# eduBoard.net
KiCad netlist of a schematic drawn in EAGLE
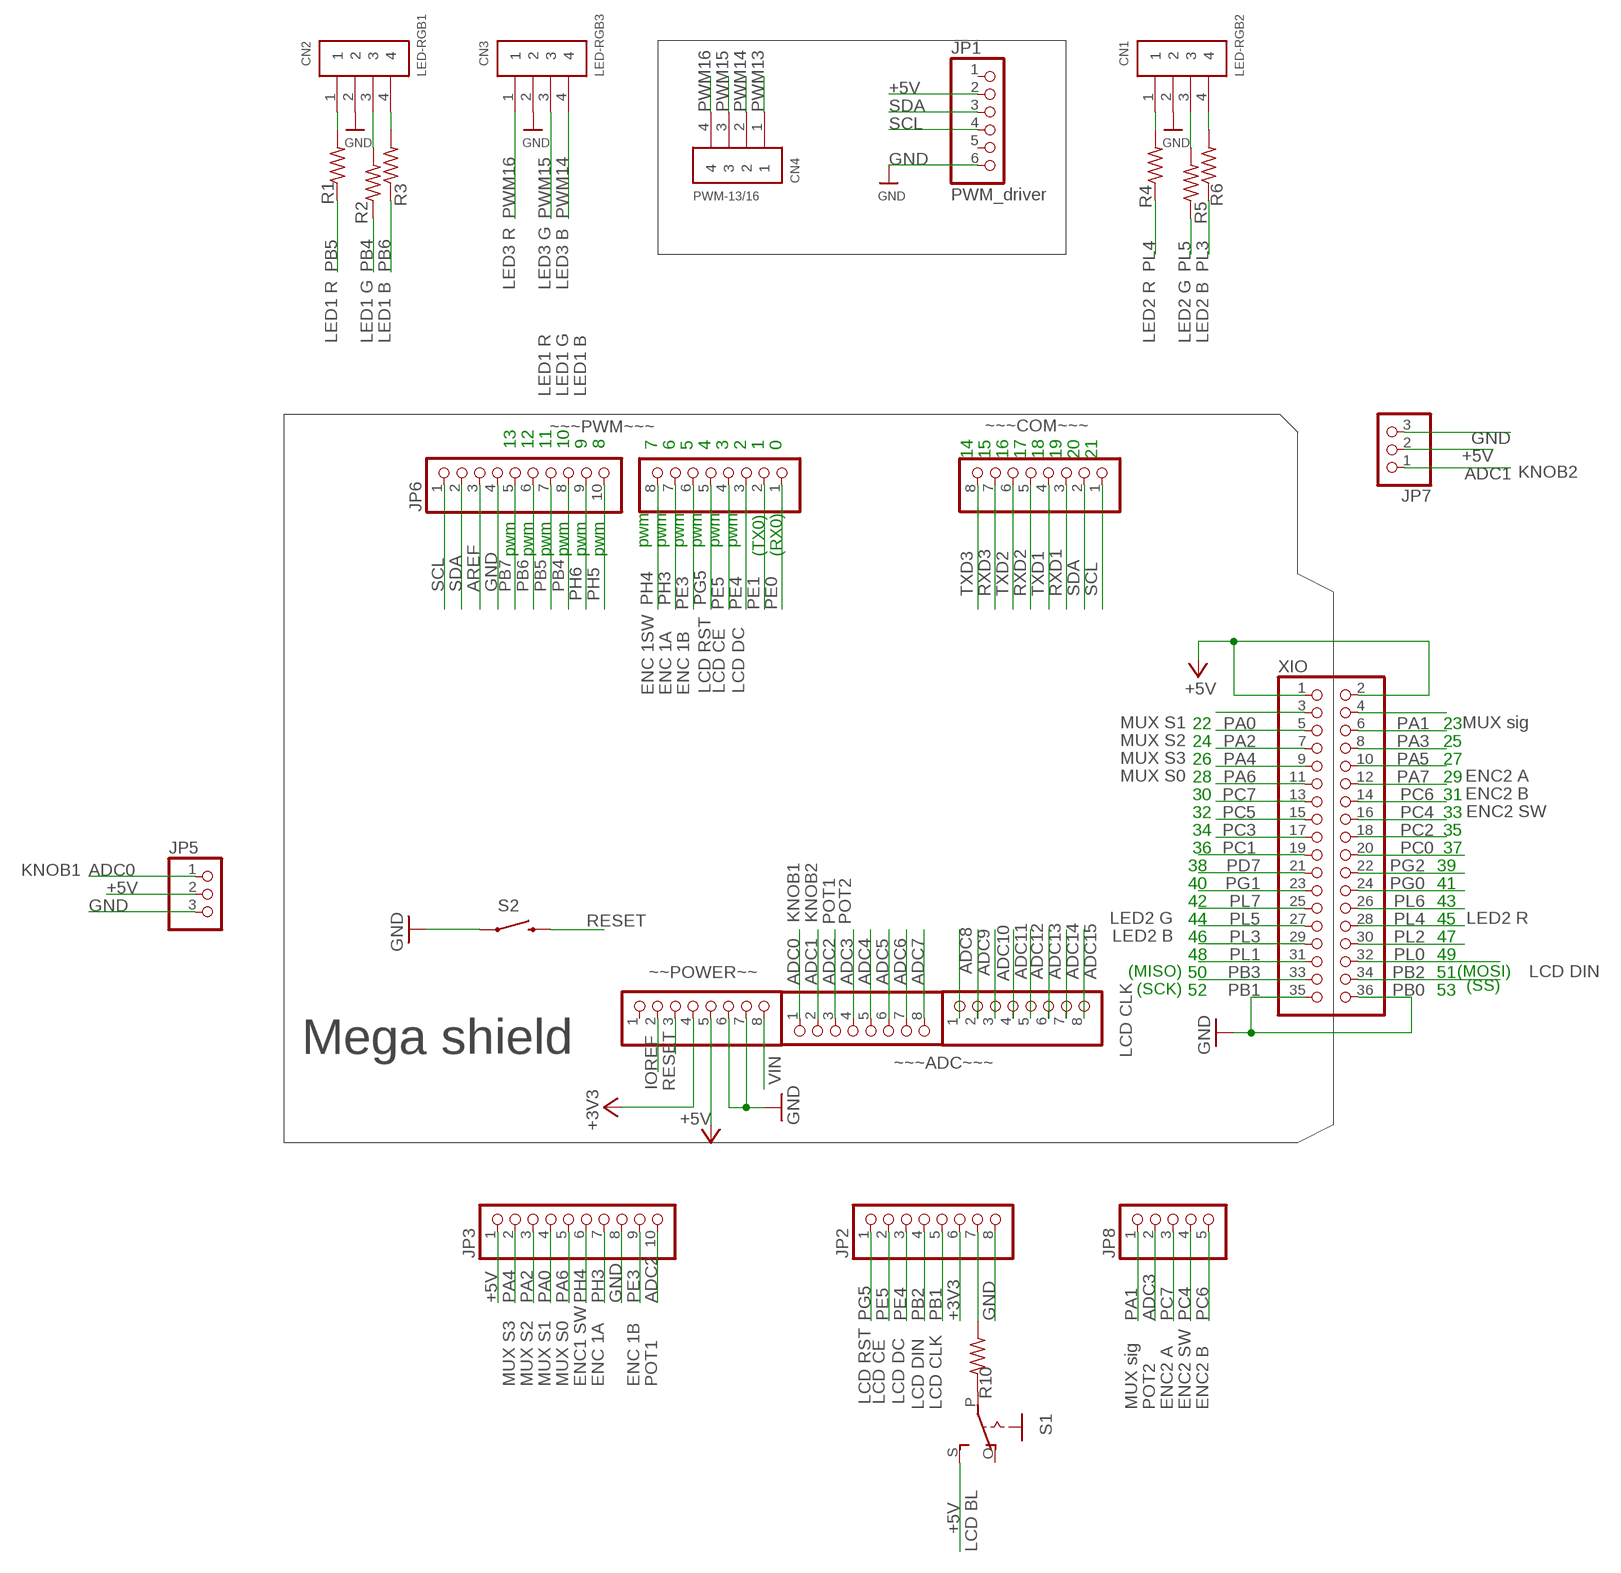
[diagram p0: schematic, sheet 1]

(export (version "E")
  (design (tool "Eeschema 10.0.6"))
  (components
    (comp (ref "ADCL")
      (value "8x1F-H8.5")
      (footprint "eagle-import:1X08")
      (libsource (lib "eagle-import") (part "PINHD-1X8"))
    )
    (comp (ref "CN1")
      (value "LED-RGB2")
      (footprint "eagle-import:1X04-BIG")
      (libsource (lib "eagle-import") (part "1X4-BIG"))
    )
    (comp (ref "CN2")
      (value "LED-RGB1")
      (footprint "eagle-import:1X04-BIG")
      (libsource (lib "eagle-import") (part "1X4-BIG"))
    )
    (comp (ref "CN3")
      (value "LED-RGB3")
      (footprint "eagle-import:1X04-BIG")
      (libsource (lib "eagle-import") (part "1X4-BIG"))
    )
    (comp (ref "CN4")
      (value "PWM-13/16")
      (footprint "eagle-import:1X04-BIG")
      (libsource (lib "eagle-import") (part "1X4-BIG"))
    )
    (comp (ref "JP1")
      (value "PWM_driver")
      (footprint "eagle-import:1X06")
      (libsource (lib "eagle-import") (part "PINHD-1X6"))
    )
    (comp (ref "JP2")
      (value "PINHD-1X8OVAL")
      (footprint "eagle-import:1X08-OVAL")
      (libsource (lib "eagle-import") (part "PINHD-1X8OVAL"))
    )
    (comp (ref "JP3")
      (value "PINHD-1X10_ARD")
      (footprint "eagle-import:1X10")
      (libsource (lib "eagle-import") (part "eduBoard_PINHD-1X10_ARD"))
    )
    (comp (ref "JP5")
      (value "PINHD-1X3")
      (footprint "eagle-import:1X03")
      (libsource (lib "eagle-import") (part "PINHD-1X3"))
    )
    (comp (ref "JP6")
      (value "10x1F-H8.5")
      (footprint "eagle-import:1X10")
      (libsource (lib "eagle-import") (part "PINHD-1X10_ARD"))
    )
    (comp (ref "JP7")
      (value "PINHD-1X3")
      (footprint "eagle-import:1X03")
      (libsource (lib "eagle-import") (part "PINHD-1X3"))
    )
    (comp (ref "JP8")
      (value "HEADER-1X5")
      (footprint "eagle-import:1X05_OVAL")
      (libsource (lib "eagle-import") (part "HEADER-1X5"))
    )
    (comp (ref "R1")
      (value "R-US_0207/10")
      (footprint "eagle-import:0207_10")
      (libsource (lib "eagle-import") (part "R-US_0207/10"))
    )
    (comp (ref "R2")
      (value "R-US_0207/10")
      (footprint "eagle-import:0207_10")
      (libsource (lib "eagle-import") (part "R-US_0207/10"))
    )
    (comp (ref "R3")
      (value "R-US_0207/10")
      (footprint "eagle-import:0207_10")
      (libsource (lib "eagle-import") (part "R-US_0207/10"))
    )
    (comp (ref "R4")
      (value "R-US_0207/10")
      (footprint "eagle-import:0207_10")
      (libsource (lib "eagle-import") (part "R-US_0207/10"))
    )
    (comp (ref "R5")
      (value "R-US_0207/10")
      (footprint "eagle-import:0207_10")
      (libsource (lib "eagle-import") (part "R-US_0207/10"))
    )
    (comp (ref "R6")
      (value "R-US_0207/10")
      (footprint "eagle-import:0207_10")
      (libsource (lib "eagle-import") (part "R-US_0207/10"))
    )
    (comp (ref "R10")
      (value "R-US_0207/10")
      (footprint "eagle-import:0207_10")
      (libsource (lib "eagle-import") (part "R-US_0207/10"))
    )
    (comp (ref "S1")
      (value "EG1218S")
      (footprint "eagle-import:EG1218")
      (libsource (lib "eagle-import") (part "EG1218S"))
    )
    (comp (ref "S2")
      (value "SWITCH-MOMENTARY-2PTH")
      (footprint "eagle-import:TACTILE-PTH")
      (libsource (lib "eagle-import") (part "SWITCH-MOMENTARY-2PTH"))
    )
    (comp (ref "XIO")
      (value "18x2F-H8.5")
      (footprint "eagle-import:2X18")
      (libsource (lib "eagle-import") (part "PINHD-2X18"))
    )
    (comp (ref "~~POWER~~")
      (value "8x1F-H8.5")
      (footprint "eagle-import:1X08")
      (libsource (lib "eagle-import") (part "PINHD-1X8"))
    )
    (comp (ref "~~~ADC~~~")
      (value "8x1F-H8.5")
      (footprint "eagle-import:1X08")
      (libsource (lib "eagle-import") (part "PINHD-1X8"))
    )
    (comp (ref "~~~COM~~~")
      (value "8x1F-H8.5")
      (footprint "eagle-import:1X08")
      (libsource (lib "eagle-import") (part "PINHD-1X8"))
    )
    (comp (ref "~~~PWM~~~")
      (value "8x1F-H8.5")
      (footprint "eagle-import:1X08")
      (libsource (lib "eagle-import") (part "PINHD-1X8"))
    )
  )
  (nets
    (net (code "1") (name "+3V3") (class "Default")
      (node (ref "JP2") (pin "6") (pinfunction "6_6") (pintype "passive"))
      (node (ref "~~POWER~~") (pin "4") (pinfunction "4_4") (pintype "passive"))
    )
    (net (code "2") (name "+5V") (class "Default")
      (node (ref "JP1") (pin "2") (pinfunction "2_2") (pintype "passive"))
      (node (ref "JP3") (pin "1") (pinfunction "1_1") (pintype "passive"))
      (node (ref "JP5") (pin "2") (pinfunction "2_2") (pintype "passive"))
      (node (ref "JP7") (pin "2") (pinfunction "2_2") (pintype "passive"))
      (node (ref "S1") (pin "S") (pinfunction "S_S") (pintype "passive"))
      (node (ref "XIO") (pin "1") (pinfunction "1_1") (pintype "passive"))
      (node (ref "XIO") (pin "2") (pinfunction "2_2") (pintype "passive"))
      (node (ref "~~POWER~~") (pin "5") (pinfunction "5_5") (pintype "passive"))
    )
    (net (code "3") (name "/ADC0") (class "Default")
      (node (ref "ADCL") (pin "1") (pinfunction "1_1") (pintype "passive"))
      (node (ref "JP5") (pin "1") (pinfunction "1_1") (pintype "passive"))
    )
    (net (code "4") (name "/ADC1") (class "Default")
      (node (ref "ADCL") (pin "2") (pinfunction "2_2") (pintype "passive"))
      (node (ref "JP7") (pin "1") (pinfunction "1_1") (pintype "passive"))
    )
    (net (code "5") (name "/ADC2") (class "Default")
      (node (ref "ADCL") (pin "3") (pinfunction "3_3") (pintype "passive"))
      (node (ref "JP3") (pin "10") (pinfunction "10_10") (pintype "passive"))
    )
    (net (code "6") (name "/ADC3") (class "Default")
      (node (ref "ADCL") (pin "4") (pinfunction "4_4") (pintype "passive"))
      (node (ref "JP8") (pin "2") (pinfunction "2_2") (pintype "passive"))
    )
    (net (code "7") (name "/ADC4") (class "Default")
      (node (ref "ADCL") (pin "5") (pinfunction "5_5") (pintype "passive"))
    )
    (net (code "8") (name "/ADC5") (class "Default")
      (node (ref "ADCL") (pin "6") (pinfunction "6_6") (pintype "passive"))
    )
    (net (code "9") (name "/ADC6") (class "Default")
      (node (ref "ADCL") (pin "7") (pinfunction "7_7") (pintype "passive"))
    )
    (net (code "10") (name "/ADC7") (class "Default")
      (node (ref "ADCL") (pin "8") (pinfunction "8_8") (pintype "passive"))
    )
    (net (code "11") (name "/ADC8") (class "Default")
      (node (ref "~~~ADC~~~") (pin "1") (pinfunction "1_1") (pintype "passive"))
    )
    (net (code "12") (name "/ADC9") (class "Default")
      (node (ref "~~~ADC~~~") (pin "2") (pinfunction "2_2") (pintype "passive"))
    )
    (net (code "13") (name "/ADC10") (class "Default")
      (node (ref "~~~ADC~~~") (pin "3") (pinfunction "3_3") (pintype "passive"))
    )
    (net (code "14") (name "/ADC11") (class "Default")
      (node (ref "~~~ADC~~~") (pin "4") (pinfunction "4_4") (pintype "passive"))
    )
    (net (code "15") (name "/ADC12") (class "Default")
      (node (ref "~~~ADC~~~") (pin "5") (pinfunction "5_5") (pintype "passive"))
    )
    (net (code "16") (name "/ADC13") (class "Default")
      (node (ref "~~~ADC~~~") (pin "6") (pinfunction "6_6") (pintype "passive"))
    )
    (net (code "17") (name "/ADC14") (class "Default")
      (node (ref "~~~ADC~~~") (pin "7") (pinfunction "7_7") (pintype "passive"))
    )
    (net (code "18") (name "/ADC15") (class "Default")
      (node (ref "~~~ADC~~~") (pin "8") (pinfunction "8_8") (pintype "passive"))
    )
    (net (code "19") (name "/AREF") (class "Default")
      (node (ref "JP6") (pin "3") (pinfunction "3_3") (pintype "passive"))
    )
    (net (code "20") (name "/IOREF") (class "Default")
      (node (ref "~~POWER~~") (pin "2") (pinfunction "2_2") (pintype "passive"))
    )
    (net (code "21") (name "/PA0") (class "Default")
      (node (ref "JP3") (pin "4") (pinfunction "4_4") (pintype "passive"))
      (node (ref "XIO") (pin "3") (pinfunction "3_3") (pintype "passive"))
    )
    (net (code "22") (name "/PA1") (class "Default")
      (node (ref "JP8") (pin "1") (pinfunction "1_1") (pintype "passive"))
      (node (ref "XIO") (pin "4") (pinfunction "4_4") (pintype "passive"))
    )
    (net (code "23") (name "/PA2") (class "Default")
      (node (ref "JP3") (pin "3") (pinfunction "3_3") (pintype "passive"))
      (node (ref "XIO") (pin "5") (pinfunction "5_5") (pintype "passive"))
    )
    (net (code "24") (name "/PA3") (class "Default")
      (node (ref "XIO") (pin "6") (pinfunction "6_6") (pintype "passive"))
    )
    (net (code "25") (name "/PA4") (class "Default")
      (node (ref "JP3") (pin "2") (pinfunction "2_2") (pintype "passive"))
      (node (ref "XIO") (pin "7") (pinfunction "7_7") (pintype "passive"))
    )
    (net (code "26") (name "/PA5") (class "Default")
      (node (ref "XIO") (pin "8") (pinfunction "8_8") (pintype "passive"))
    )
    (net (code "27") (name "/PA6") (class "Default")
      (node (ref "JP3") (pin "5") (pinfunction "5_5") (pintype "passive"))
      (node (ref "XIO") (pin "9") (pinfunction "9_9") (pintype "passive"))
    )
    (net (code "28") (name "/PA7") (class "Default")
      (node (ref "XIO") (pin "10") (pinfunction "10_10") (pintype "passive"))
    )
    (net (code "29") (name "/PB0") (class "Default")
      (node (ref "XIO") (pin "34") (pinfunction "34_34") (pintype "passive"))
    )
    (net (code "30") (name "/PB1") (class "Default")
      (node (ref "JP2") (pin "5") (pinfunction "5_5") (pintype "passive"))
      (node (ref "XIO") (pin "33") (pinfunction "33_33") (pintype "passive"))
    )
    (net (code "31") (name "/PB2") (class "Default")
      (node (ref "JP2") (pin "4") (pinfunction "4_4") (pintype "passive"))
      (node (ref "XIO") (pin "32") (pinfunction "32_32") (pintype "passive"))
    )
    (net (code "32") (name "/PB3") (class "Default")
      (node (ref "XIO") (pin "31") (pinfunction "31_31") (pintype "passive"))
    )
    (net (code "33") (name "/PB4") (class "Default")
      (node (ref "JP6") (pin "8") (pinfunction "8_8") (pintype "passive"))
      (node (ref "R2") (pin "1") (pinfunction "1_1") (pintype "passive"))
    )
    (net (code "34") (name "/PB5") (class "Default")
      (node (ref "JP6") (pin "7") (pinfunction "7_7") (pintype "passive"))
      (node (ref "R1") (pin "1") (pinfunction "1_1") (pintype "passive"))
    )
    (net (code "35") (name "/PB6") (class "Default")
      (node (ref "JP6") (pin "6") (pinfunction "6_6") (pintype "passive"))
      (node (ref "R3") (pin "1") (pinfunction "1_1") (pintype "passive"))
    )
    (net (code "36") (name "/PB7") (class "Default")
      (node (ref "JP6") (pin "5") (pinfunction "5_5") (pintype "passive"))
    )
    (net (code "37") (name "/PC0") (class "Default")
      (node (ref "XIO") (pin "18") (pinfunction "18_18") (pintype "passive"))
    )
    (net (code "38") (name "/PC1") (class "Default")
      (node (ref "XIO") (pin "17") (pinfunction "17_17") (pintype "passive"))
    )
    (net (code "39") (name "/PC2") (class "Default")
      (node (ref "XIO") (pin "16") (pinfunction "16_16") (pintype "passive"))
    )
    (net (code "40") (name "/PC3") (class "Default")
      (node (ref "XIO") (pin "15") (pinfunction "15_15") (pintype "passive"))
    )
    (net (code "41") (name "/PC4") (class "Default")
      (node (ref "JP8") (pin "4") (pinfunction "4_4") (pintype "passive"))
      (node (ref "XIO") (pin "14") (pinfunction "14_14") (pintype "passive"))
    )
    (net (code "42") (name "/PC5") (class "Default")
      (node (ref "XIO") (pin "13") (pinfunction "13_13") (pintype "passive"))
    )
    (net (code "43") (name "/PC6") (class "Default")
      (node (ref "JP8") (pin "5") (pinfunction "5_5") (pintype "passive"))
      (node (ref "XIO") (pin "12") (pinfunction "12_12") (pintype "passive"))
    )
    (net (code "44") (name "/PC7") (class "Default")
      (node (ref "JP8") (pin "3") (pinfunction "3_3") (pintype "passive"))
      (node (ref "XIO") (pin "11") (pinfunction "11_11") (pintype "passive"))
    )
    (net (code "45") (name "/PD7") (class "Default")
      (node (ref "XIO") (pin "19") (pinfunction "19_19") (pintype "passive"))
    )
    (net (code "46") (name "/PE0") (class "Default")
      (node (ref "~~~PWM~~~") (pin "1") (pinfunction "1_1") (pintype "passive"))
    )
    (net (code "47") (name "/PE1") (class "Default")
      (node (ref "~~~PWM~~~") (pin "2") (pinfunction "2_2") (pintype "passive"))
    )
    (net (code "48") (name "/PE3") (class "Default")
      (node (ref "JP3") (pin "9") (pinfunction "9_9") (pintype "passive"))
      (node (ref "~~~PWM~~~") (pin "6") (pinfunction "6_6") (pintype "passive"))
    )
    (net (code "49") (name "/PE4") (class "Default")
      (node (ref "JP2") (pin "3") (pinfunction "3_3") (pintype "passive"))
      (node (ref "~~~PWM~~~") (pin "3") (pinfunction "3_3") (pintype "passive"))
    )
    (net (code "50") (name "/PE5") (class "Default")
      (node (ref "JP2") (pin "2") (pinfunction "2_2") (pintype "passive"))
      (node (ref "~~~PWM~~~") (pin "4") (pinfunction "4_4") (pintype "passive"))
    )
    (net (code "51") (name "/PG0") (class "Default")
      (node (ref "XIO") (pin "22") (pinfunction "22_22") (pintype "passive"))
    )
    (net (code "52") (name "/PG1") (class "Default")
      (node (ref "XIO") (pin "21") (pinfunction "21_21") (pintype "passive"))
    )
    (net (code "53") (name "/PG2") (class "Default")
      (node (ref "XIO") (pin "20") (pinfunction "20_20") (pintype "passive"))
    )
    (net (code "54") (name "/PG5") (class "Default")
      (node (ref "JP2") (pin "1") (pinfunction "1_1") (pintype "passive"))
      (node (ref "~~~PWM~~~") (pin "5") (pinfunction "5_5") (pintype "passive"))
    )
    (net (code "55") (name "/PH3") (class "Default")
      (node (ref "JP3") (pin "7") (pinfunction "7_7") (pintype "passive"))
      (node (ref "~~~PWM~~~") (pin "7") (pinfunction "7_7") (pintype "passive"))
    )
    (net (code "56") (name "/PH4") (class "Default")
      (node (ref "JP3") (pin "6") (pinfunction "6_6") (pintype "passive"))
      (node (ref "~~~PWM~~~") (pin "8") (pinfunction "8_8") (pintype "passive"))
    )
    (net (code "57") (name "/PH5") (class "Default")
      (node (ref "JP6") (pin "10") (pinfunction "10_10") (pintype "passive"))
    )
    (net (code "58") (name "/PH6") (class "Default")
      (node (ref "JP6") (pin "9") (pinfunction "9_9") (pintype "passive"))
    )
    (net (code "59") (name "/PL0") (class "Default")
      (node (ref "XIO") (pin "30") (pinfunction "30_30") (pintype "passive"))
    )
    (net (code "60") (name "/PL1") (class "Default")
      (node (ref "XIO") (pin "29") (pinfunction "29_29") (pintype "passive"))
    )
    (net (code "61") (name "/PL2") (class "Default")
      (node (ref "XIO") (pin "28") (pinfunction "28_28") (pintype "passive"))
    )
    (net (code "62") (name "/PL3") (class "Default")
      (node (ref "R6") (pin "1") (pinfunction "1_1") (pintype "passive"))
      (node (ref "XIO") (pin "27") (pinfunction "27_27") (pintype "passive"))
    )
    (net (code "63") (name "/PL4") (class "Default")
      (node (ref "R4") (pin "1") (pinfunction "1_1") (pintype "passive"))
      (node (ref "XIO") (pin "26") (pinfunction "26_26") (pintype "passive"))
    )
    (net (code "64") (name "/PL5") (class "Default")
      (node (ref "R5") (pin "1") (pinfunction "1_1") (pintype "passive"))
      (node (ref "XIO") (pin "25") (pinfunction "25_25") (pintype "passive"))
    )
    (net (code "65") (name "/PL6") (class "Default")
      (node (ref "XIO") (pin "24") (pinfunction "24_24") (pintype "passive"))
    )
    (net (code "66") (name "/PL7") (class "Default")
      (node (ref "XIO") (pin "23") (pinfunction "23_23") (pintype "passive"))
    )
    (net (code "67") (name "/PWM13") (class "Default")
      (node (ref "CN4") (pin "1") (pinfunction "1_1") (pintype "bidirectional"))
    )
    (net (code "68") (name "/PWM14") (class "Default")
      (node (ref "CN3") (pin "4") (pinfunction "4_4") (pintype "bidirectional"))
      (node (ref "CN4") (pin "2") (pinfunction "2_2") (pintype "bidirectional"))
    )
    (net (code "69") (name "/PWM15") (class "Default")
      (node (ref "CN3") (pin "3") (pinfunction "3_3") (pintype "bidirectional"))
      (node (ref "CN4") (pin "3") (pinfunction "3_3") (pintype "bidirectional"))
    )
    (net (code "70") (name "/PWM16") (class "Default")
      (node (ref "CN3") (pin "1") (pinfunction "1_1") (pintype "bidirectional"))
      (node (ref "CN4") (pin "4") (pinfunction "4_4") (pintype "bidirectional"))
    )
    (net (code "71") (name "/RESET") (class "Default")
      (node (ref "S2") (pin "3") (pinfunction "2_3") (pintype "passive"))
      (node (ref "~~POWER~~") (pin "3") (pinfunction "3_3") (pintype "passive"))
    )
    (net (code "72") (name "/RXD1") (class "Default")
      (node (ref "~~~COM~~~") (pin "3") (pinfunction "3_3") (pintype "passive"))
    )
    (net (code "73") (name "/RXD2") (class "Default")
      (node (ref "~~~COM~~~") (pin "5") (pinfunction "5_5") (pintype "passive"))
    )
    (net (code "74") (name "/RXD3") (class "Default")
      (node (ref "~~~COM~~~") (pin "7") (pinfunction "7_7") (pintype "passive"))
    )
    (net (code "75") (name "/SCL") (class "Default")
      (node (ref "JP1") (pin "4") (pinfunction "4_4") (pintype "passive"))
      (node (ref "JP6") (pin "1") (pinfunction "1_1") (pintype "passive"))
      (node (ref "~~~COM~~~") (pin "1") (pinfunction "1_1") (pintype "passive"))
    )
    (net (code "76") (name "/SDA") (class "Default")
      (node (ref "JP1") (pin "3") (pinfunction "3_3") (pintype "passive"))
      (node (ref "JP6") (pin "2") (pinfunction "2_2") (pintype "passive"))
      (node (ref "~~~COM~~~") (pin "2") (pinfunction "2_2") (pintype "passive"))
    )
    (net (code "77") (name "/TXD1") (class "Default")
      (node (ref "~~~COM~~~") (pin "4") (pinfunction "4_4") (pintype "passive"))
    )
    (net (code "78") (name "/TXD2") (class "Default")
      (node (ref "~~~COM~~~") (pin "6") (pinfunction "6_6") (pintype "passive"))
    )
    (net (code "79") (name "/TXD3") (class "Default")
      (node (ref "~~~COM~~~") (pin "8") (pinfunction "8_8") (pintype "passive"))
    )
    (net (code "80") (name "/VIN") (class "Default")
      (node (ref "~~POWER~~") (pin "8") (pinfunction "8_8") (pintype "passive"))
    )
    (net (code "81") (name "GND") (class "Default")
      (node (ref "CN1") (pin "2") (pinfunction "2_2") (pintype "bidirectional"))
      (node (ref "CN2") (pin "2") (pinfunction "2_2") (pintype "bidirectional"))
      (node (ref "CN3") (pin "2") (pinfunction "2_2") (pintype "bidirectional"))
      (node (ref "JP1") (pin "6") (pinfunction "6_6") (pintype "passive"))
      (node (ref "JP2") (pin "8") (pinfunction "8_8") (pintype "passive"))
      (node (ref "JP3") (pin "8") (pinfunction "8_8") (pintype "passive"))
      (node (ref "JP5") (pin "3") (pinfunction "3_3") (pintype "passive"))
      (node (ref "JP6") (pin "4") (pinfunction "4_4") (pintype "passive"))
      (node (ref "JP7") (pin "3") (pinfunction "3_3") (pintype "passive"))
      (node (ref "S2") (pin "1") (pinfunction "1_1") (pintype "passive"))
      (node (ref "XIO") (pin "35") (pinfunction "35_35") (pintype "passive"))
      (node (ref "XIO") (pin "36") (pinfunction "36_36") (pintype "passive"))
      (node (ref "~~POWER~~") (pin "6") (pinfunction "6_6") (pintype "passive"))
      (node (ref "~~POWER~~") (pin "7") (pinfunction "7_7") (pintype "passive"))
    )
    (net (code "82") (name "Net-(CN1-Pad1)") (class "Default")
      (node (ref "CN1") (pin "1") (pinfunction "1_1") (pintype "bidirectional"))
      (node (ref "R4") (pin "2") (pinfunction "2_2") (pintype "passive"))
    )
    (net (code "83") (name "Net-(CN1-Pad3)") (class "Default")
      (node (ref "CN1") (pin "3") (pinfunction "3_3") (pintype "bidirectional"))
      (node (ref "R5") (pin "2") (pinfunction "2_2") (pintype "passive"))
    )
    (net (code "84") (name "Net-(CN1-Pad4)") (class "Default")
      (node (ref "CN1") (pin "4") (pinfunction "4_4") (pintype "bidirectional"))
      (node (ref "R6") (pin "2") (pinfunction "2_2") (pintype "passive"))
    )
    (net (code "85") (name "Net-(CN2-Pad1)") (class "Default")
      (node (ref "CN2") (pin "1") (pinfunction "1_1") (pintype "bidirectional"))
      (node (ref "R1") (pin "2") (pinfunction "2_2") (pintype "passive"))
    )
    (net (code "86") (name "Net-(CN2-Pad3)") (class "Default")
      (node (ref "CN2") (pin "3") (pinfunction "3_3") (pintype "bidirectional"))
      (node (ref "R2") (pin "2") (pinfunction "2_2") (pintype "passive"))
    )
    (net (code "87") (name "Net-(CN2-Pad4)") (class "Default")
      (node (ref "CN2") (pin "4") (pinfunction "4_4") (pintype "bidirectional"))
      (node (ref "R3") (pin "2") (pinfunction "2_2") (pintype "passive"))
    )
    (net (code "88") (name "Net-(JP2-Pad7)") (class "Default")
      (node (ref "JP2") (pin "7") (pinfunction "7_7") (pintype "passive"))
      (node (ref "R10") (pin "2") (pinfunction "2_2") (pintype "passive"))
    )
    (net (code "89") (name "Net-(R10-Pad1)") (class "Default")
      (node (ref "R10") (pin "1") (pinfunction "1_1") (pintype "passive"))
      (node (ref "S1") (pin "P") (pinfunction "P_P") (pintype "passive"))
    )
    (net (code "90") (name "unconnected-(JP1-Pad1)") (class "Default")
      (node (ref "JP1") (pin "1") (pinfunction "1_1") (pintype "passive"))
    )
    (net (code "91") (name "unconnected-(JP1-Pad5)") (class "Default")
      (node (ref "JP1") (pin "5") (pinfunction "5_5") (pintype "passive"))
    )
    (net (code "92") (name "unconnected-(S1-PadO)") (class "Default")
      (node (ref "S1") (pin "O") (pinfunction "O_O") (pintype "passive"))
    )
    (net (code "93") (name "unconnected-(~~POWER~~-Pad1)") (class "Default")
      (node (ref "~~POWER~~") (pin "1") (pinfunction "1_1") (pintype "passive"))
    )
  )
)
